# Thermocouple.net
KiCad netlist of a schematic drawn in EAGLE
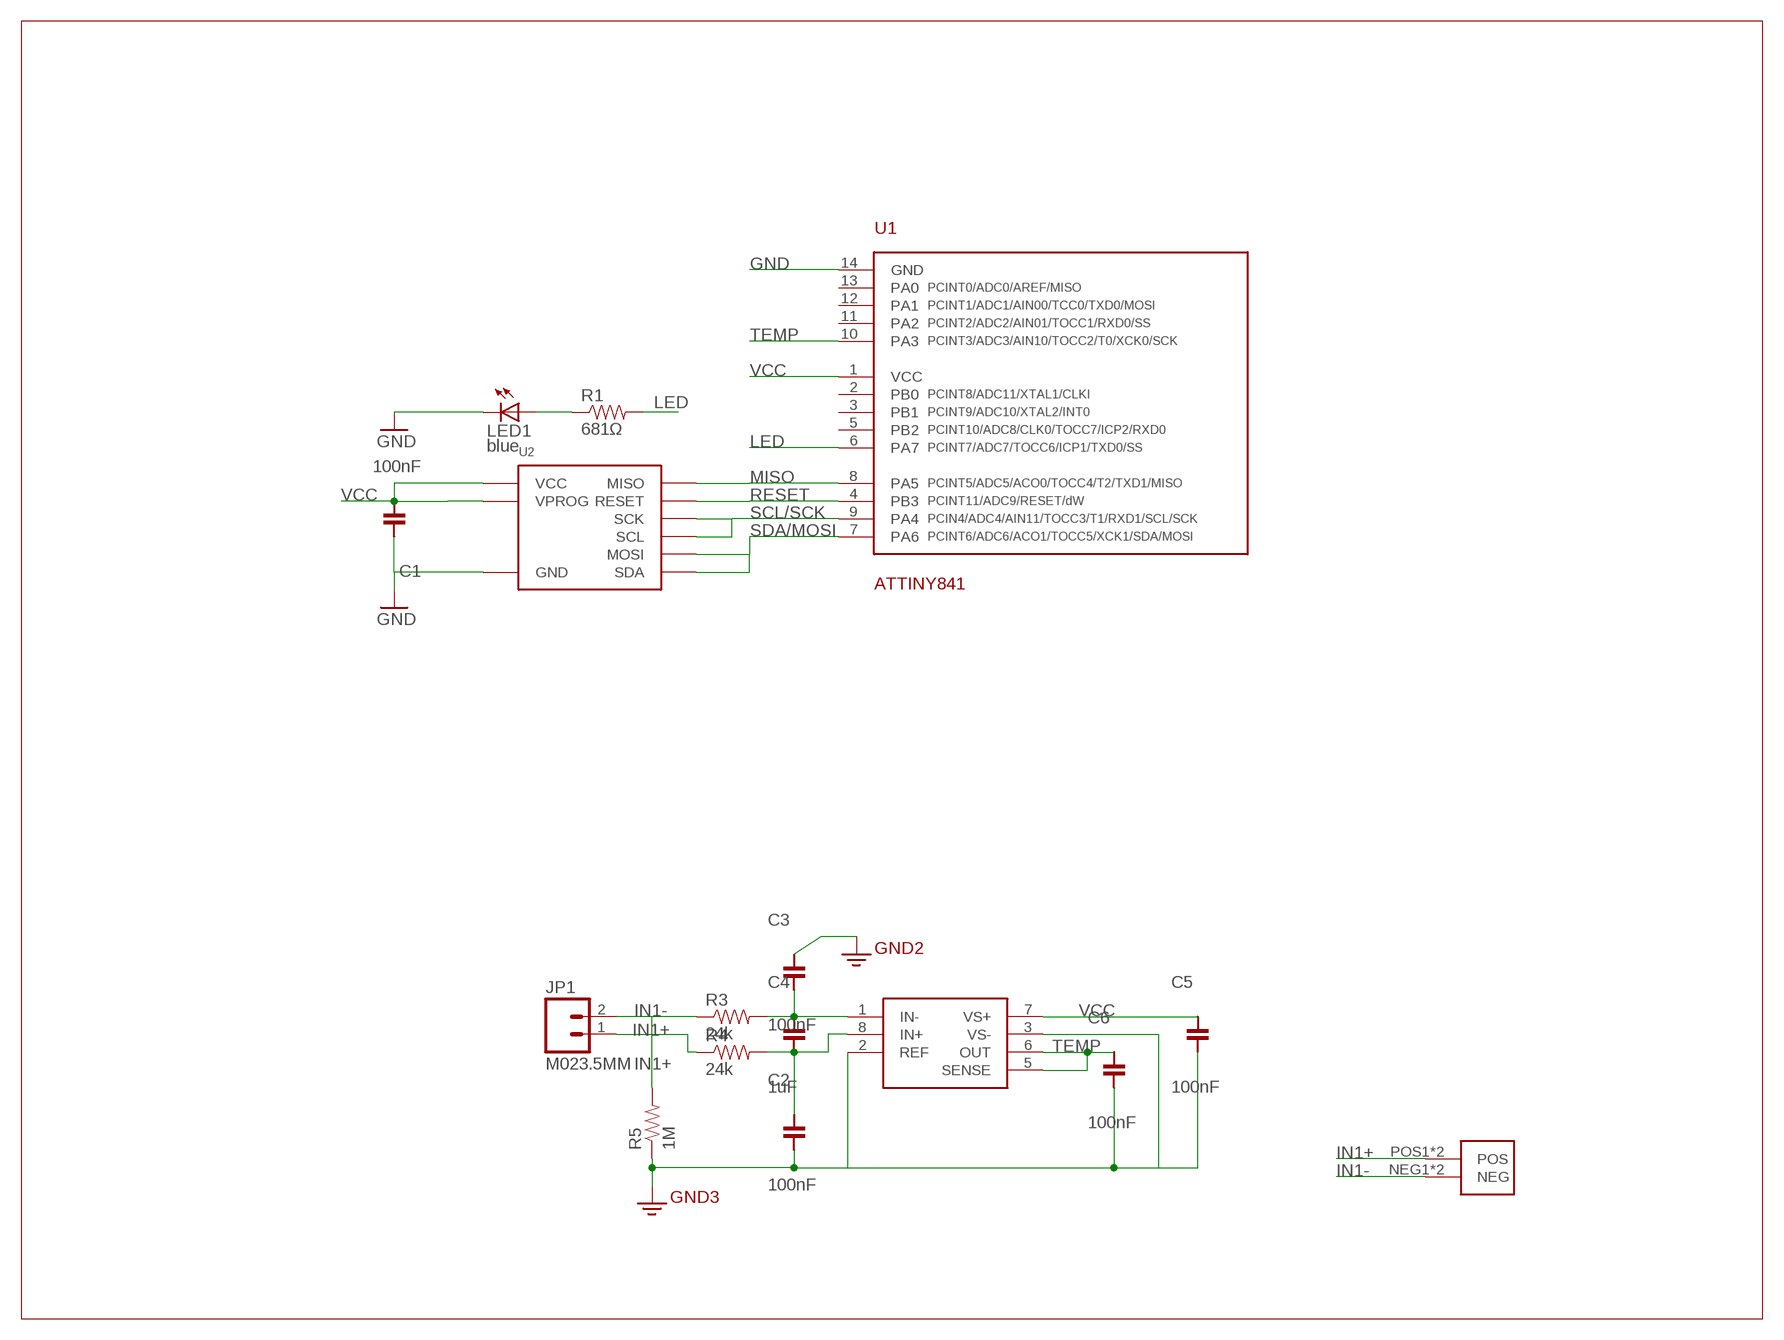
[diagram p0: schematic, sheet 1]

(export (version "E")
  (design (tool "Eeschema 10.0.6"))
  (components
    (comp (ref "C1")
      (value "100nF")
      (footprint "eagle-import:0603")
      (fields (field (name "PARTNUM") "C0603C104K5RACTU"))
      (libsource (lib "eagle-import") (part "CAPACITOR-100NF"))
    )
    (comp (ref "C2")
      (value "100nF")
      (footprint "eagle-import:0603")
      (fields (field (name "PARTNUM") "C0603C104K5RACTU"))
      (libsource (lib "eagle-import") (part "CAPACITOR-100NF"))
    )
    (comp (ref "C3")
      (value "100nF")
      (footprint "eagle-import:0603")
      (fields (field (name "PARTNUM") "C0603C104K5RACTU"))
      (libsource (lib "eagle-import") (part "CAPACITOR-100NF"))
    )
    (comp (ref "C4")
      (value "1uF")
      (footprint "eagle-import:0603")
      (fields (field (name "PARTNUM") "C0603C105K4RACTU"))
      (libsource (lib "eagle-import") (part "CAPACITOR-1UF"))
    )
    (comp (ref "C5")
      (value "100nF")
      (footprint "eagle-import:0603")
      (fields (field (name "PARTNUM") "C0603C104K5RACTU"))
      (libsource (lib "eagle-import") (part "CAPACITOR-100NF"))
    )
    (comp (ref "C6")
      (value "100nF")
      (footprint "eagle-import:0603")
      (fields (field (name "PARTNUM") "C0603C104K5RACTU"))
      (libsource (lib "eagle-import") (part "CAPACITOR-100NF"))
    )
    (comp (ref "JP1")
      (value "M023.5MM")
      (footprint "eagle-import:SCREWTERMINAL-3.5MM-2")
      (fields (field (name "PARTNUM") "OSTTE020104"))
      (libsource (lib "eagle-import") (part "M023.5MM"))
    )
    (comp (ref "LED1")
      (value "blue")
      (footprint "eagle-import:0805-LED")
      (fields (field (name "PARTNUM") "LTST-C171TBKT"))
      (libsource (lib "eagle-import") (part "LED-0805-BLUE"))
    )
    (comp (ref "R1")
      (value "681Ω")
      (footprint "eagle-import:0603")
      (fields (field (name "PARTNUM") "ERJ-3EKF6810V"))
      (libsource (lib "eagle-import") (part "RESISTOR-681Ω"))
    )
    (comp (ref "R3")
      (value "24k")
      (footprint "eagle-import:0603")
      (fields (field (name "PARTNUM") "ERJ-3EKF2402V"))
      (libsource (lib "eagle-import") (part "RESISTOR-0603"))
    )
    (comp (ref "R4")
      (value "24k")
      (footprint "eagle-import:0603")
      (fields (field (name "PARTNUM") "ERJ-3EKF2402V"))
      (libsource (lib "eagle-import") (part "RESISTOR-0603"))
    )
    (comp (ref "R5")
      (value "1M")
      (footprint "eagle-import:0603")
      (fields (field (name "PARTNUM") "ERJ-3EKF1004V"))
      (libsource (lib "eagle-import") (part "RESISTOR-0603"))
    )
    (comp (ref "U$1")
      (value "AD8495")
      (footprint "eagle-import:MSOP-8")
      (fields (field (name "PARTNUM") "AD8495ARMZ-R7"))
      (libsource (lib "eagle-import") (part "AD8495"))
    )
    (comp (ref "U$4")
      (value "THERMOCOUPLE-JACK")
      (footprint "eagle-import:THERMOCOUPLE-JACK")
      (fields (field (name "PARTNUM") "Keystone 3572, 3549"))
      (libsource (lib "eagle-import") (part "THERMOCOUPLE-JACK"))
    )
    (comp (ref "U1")
      (value "ATTINY841")
      (footprint "eagle-import:SOIC-14")
      (fields (field (name "PARTNUM") "ATTINY841-SSUR"))
      (libsource (lib "eagle-import") (part "ATTINY841"))
    )
    (comp (ref "U2")
      (value "EXCLUDE")
      (footprint "eagle-import:DEVICE-PCB")
      (libsource (lib "eagle-import") (part "DEVICE-PCB"))
    )
  )
  (nets
    (net (code "1") (name "/IN1+") (class "Default")
      (node (ref "JP1") (pin "1") (pinfunction "1_1") (pintype "passive"))
      (node (ref "R4") (pin "1") (pinfunction "1_1") (pintype "passive"))
      (node (ref "U$4") (pin "POS1") (pinfunction "POS_POS1") (pintype "bidirectional"))
      (node (ref "U$4") (pin "POS2") (pinfunction "POS_POS2") (pintype "bidirectional"))
    )
    (net (code "2") (name "/IN1-") (class "Default")
      (node (ref "JP1") (pin "2") (pinfunction "2_2") (pintype "passive"))
      (node (ref "R3") (pin "1") (pinfunction "1_1") (pintype "passive"))
      (node (ref "R5") (pin "2") (pinfunction "2_2") (pintype "passive"))
      (node (ref "U$4") (pin "NEG1") (pinfunction "NEG_NEG1") (pintype "bidirectional"))
      (node (ref "U$4") (pin "NEG2") (pinfunction "NEG_NEG2") (pintype "bidirectional"))
    )
    (net (code "3") (name "/LED") (class "Default")
      (node (ref "R1") (pin "2") (pinfunction "2_2") (pintype "passive"))
      (node (ref "U1") (pin "6") (pinfunction "PA7_6") (pintype "bidirectional"))
    )
    (net (code "4") (name "/MISO") (class "Default")
      (node (ref "U1") (pin "8") (pinfunction "PA5_8") (pintype "bidirectional"))
      (node (ref "U2") (pin "PROG3") (pinfunction "MISO_PROG3") (pintype "bidirectional"))
    )
    (net (code "5") (name "/RESET") (class "Default")
      (node (ref "U1") (pin "4") (pinfunction "PB3_4") (pintype "bidirectional"))
      (node (ref "U2") (pin "PROG1") (pinfunction "RESET_PROG1") (pintype "bidirectional"))
    )
    (net (code "6") (name "/SCL{slash}SCK") (class "Default")
      (node (ref "U1") (pin "9") (pinfunction "PA4_9") (pintype "bidirectional"))
      (node (ref "U2") (pin "BUS3") (pinfunction "SCL_BUS3") (pintype "bidirectional"))
      (node (ref "U2") (pin "PROG2") (pinfunction "SCK_PROG2") (pintype "bidirectional"))
    )
    (net (code "7") (name "/SDA{slash}MOSI") (class "Default")
      (node (ref "U1") (pin "7") (pinfunction "PA6_7") (pintype "bidirectional"))
      (node (ref "U2") (pin "BUS1") (pinfunction "SDA_BUS1") (pintype "bidirectional"))
      (node (ref "U2") (pin "PROG4") (pinfunction "MOSI_PROG4") (pintype "bidirectional"))
    )
    (net (code "8") (name "/TEMP") (class "Default")
      (node (ref "C6") (pin "1") (pinfunction "1_1") (pintype "passive"))
      (node (ref "U$1") (pin "5") (pinfunction "SENSE_5") (pintype "bidirectional"))
      (node (ref "U$1") (pin "6") (pinfunction "OUT_6") (pintype "bidirectional"))
      (node (ref "U1") (pin "10") (pinfunction "PA3_10") (pintype "bidirectional"))
    )
    (net (code "9") (name "/VCC") (class "Default")
      (node (ref "C1") (pin "2") (pinfunction "2_2") (pintype "passive"))
      (node (ref "C5") (pin "1") (pinfunction "1_1") (pintype "passive"))
      (node (ref "U$1") (pin "7") (pinfunction "VS+_7") (pintype "bidirectional"))
      (node (ref "U1") (pin "1") (pinfunction "VCC_1") (pintype "bidirectional"))
      (node (ref "U2") (pin "BUS2") (pinfunction "VCC_BUS2") (pintype "bidirectional"))
      (node (ref "U2") (pin "PROG0") (pinfunction "VPROG_PROG0") (pintype "bidirectional"))
    )
    (net (code "10") (name "GND") (class "Default")
      (node (ref "C1") (pin "1") (pinfunction "1_1") (pintype "passive"))
      (node (ref "C2") (pin "2") (pinfunction "2_2") (pintype "passive"))
      (node (ref "C3") (pin "1") (pinfunction "1_1") (pintype "passive"))
      (node (ref "C5") (pin "2") (pinfunction "2_2") (pintype "passive"))
      (node (ref "C6") (pin "2") (pinfunction "2_2") (pintype "passive"))
      (node (ref "LED1") (pin "C") (pinfunction "C_C") (pintype "passive"))
      (node (ref "R5") (pin "1") (pinfunction "1_1") (pintype "passive"))
      (node (ref "U$1") (pin "2") (pinfunction "REF_2") (pintype "bidirectional"))
      (node (ref "U$1") (pin "3") (pinfunction "VS-_3") (pintype "bidirectional"))
      (node (ref "U1") (pin "14") (pinfunction "GND_14") (pintype "bidirectional"))
      (node (ref "U2") (pin "BUS0") (pinfunction "GND_BUS0") (pintype "bidirectional"))
    )
    (net (code "11") (name "Net-(LED1-PadA)") (class "Default")
      (node (ref "LED1") (pin "A") (pinfunction "A_A") (pintype "passive"))
      (node (ref "R1") (pin "1") (pinfunction "1_1") (pintype "passive"))
    )
    (net (code "12") (name "Net-(U$1-IN+)") (class "Default")
      (node (ref "C2") (pin "1") (pinfunction "1_1") (pintype "passive"))
      (node (ref "C4") (pin "2") (pinfunction "2_2") (pintype "passive"))
      (node (ref "R4") (pin "2") (pinfunction "2_2") (pintype "passive"))
      (node (ref "U$1") (pin "8") (pinfunction "IN+_8") (pintype "bidirectional"))
    )
    (net (code "13") (name "Net-(U$1-IN-)") (class "Default")
      (node (ref "C3") (pin "2") (pinfunction "2_2") (pintype "passive"))
      (node (ref "C4") (pin "1") (pinfunction "1_1") (pintype "passive"))
      (node (ref "R3") (pin "2") (pinfunction "2_2") (pintype "passive"))
      (node (ref "U$1") (pin "1") (pinfunction "IN-_1") (pintype "bidirectional"))
    )
    (net (code "14") (name "unconnected-(U1-PA0-Pad13)") (class "Default")
      (node (ref "U1") (pin "13") (pinfunction "PA0_13") (pintype "bidirectional"))
    )
    (net (code "15") (name "unconnected-(U1-PA1-Pad12)") (class "Default")
      (node (ref "U1") (pin "12") (pinfunction "PA1_12") (pintype "bidirectional"))
    )
    (net (code "16") (name "unconnected-(U1-PA2-Pad11)") (class "Default")
      (node (ref "U1") (pin "11") (pinfunction "PA2_11") (pintype "bidirectional"))
    )
    (net (code "17") (name "unconnected-(U1-PB0-Pad2)") (class "Default")
      (node (ref "U1") (pin "2") (pinfunction "PB0_2") (pintype "bidirectional"))
    )
    (net (code "18") (name "unconnected-(U1-PB1-Pad3)") (class "Default")
      (node (ref "U1") (pin "3") (pinfunction "PB1_3") (pintype "bidirectional"))
    )
    (net (code "19") (name "unconnected-(U1-PB2-Pad5)") (class "Default")
      (node (ref "U1") (pin "5") (pinfunction "PB2_5") (pintype "bidirectional"))
    )
  )
)
